# untitled.net
KiCad netlist of a schematic drawn in EAGLE
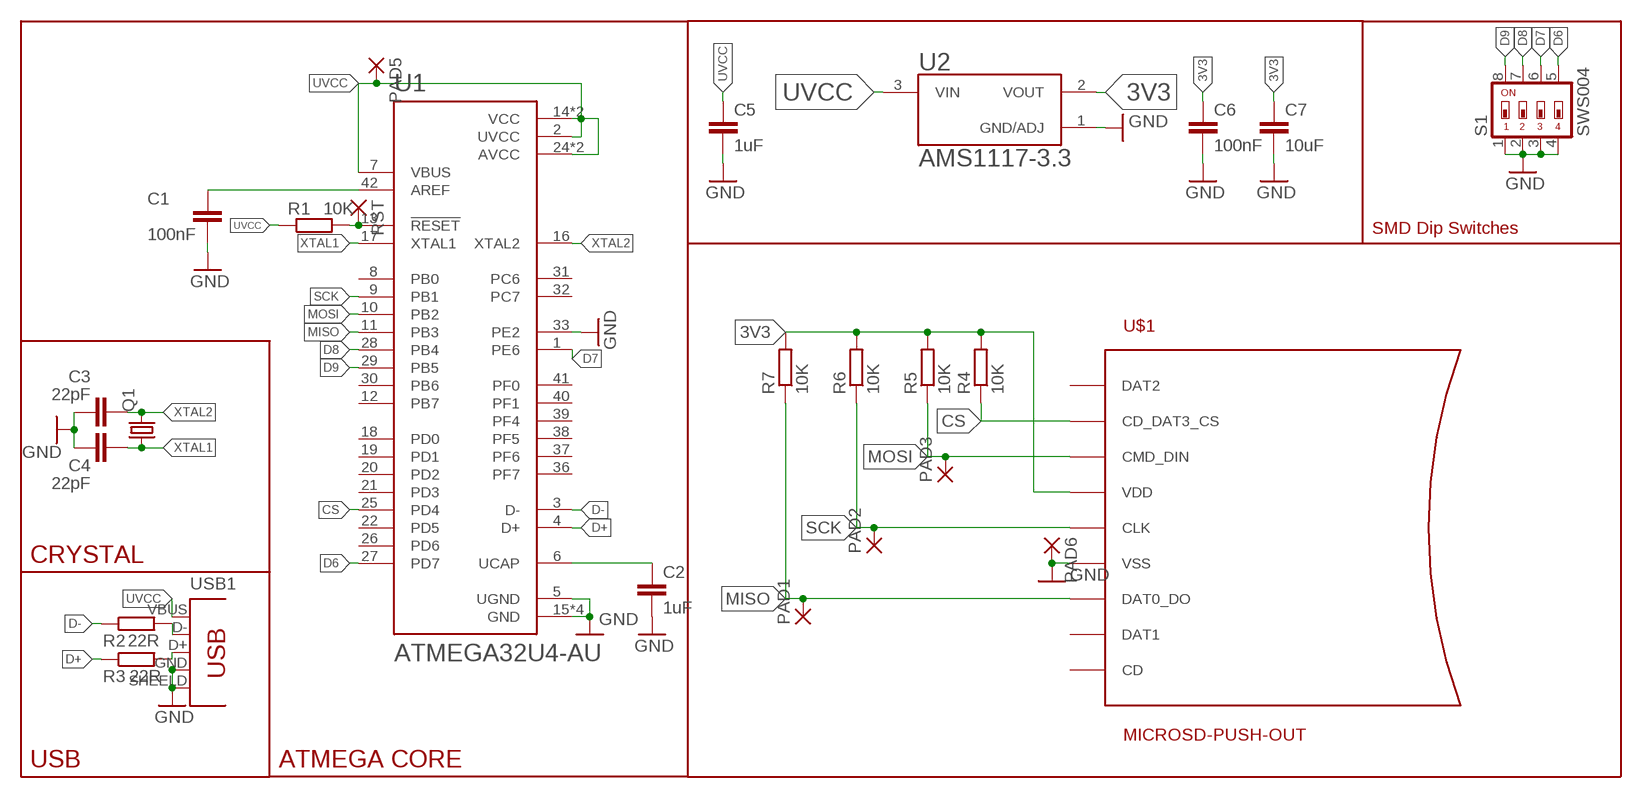
[diagram p0: schematic, sheet 1]

(export (version "E")
  (design (tool "Eeschema 10.0.6"))
  (components
    (comp (ref "C1")
      (value "100nF")
      (footprint "eagle-import:C0603")
      (libsource (lib "eagle-import") (part "C-EUC0603"))
    )
    (comp (ref "C2")
      (value "1uF")
      (footprint "eagle-import:C0603")
      (libsource (lib "eagle-import") (part "C-EUC0603"))
    )
    (comp (ref "C3")
      (value "22pF")
      (footprint "eagle-import:C0603")
      (libsource (lib "eagle-import") (part "C-EUC0603"))
    )
    (comp (ref "C4")
      (value "22pF")
      (footprint "eagle-import:C0603")
      (libsource (lib "eagle-import") (part "C-EUC0603"))
    )
    (comp (ref "C5")
      (value "1uF")
      (footprint "eagle-import:C0603")
      (libsource (lib "eagle-import") (part "C-EUC0603"))
    )
    (comp (ref "C6")
      (value "100nF")
      (footprint "eagle-import:C0603")
      (libsource (lib "eagle-import") (part "C-EUC0603"))
    )
    (comp (ref "C7")
      (value "10uF")
      (footprint "eagle-import:C0603")
      (libsource (lib "eagle-import") (part "C-EUC0603"))
    )
    (comp (ref "PAD1")
      (value "1,6/0,8")
      (footprint "eagle-import:1,6_0,8")
      (libsource (lib "eagle-import") (part "1,6/0,8"))
    )
    (comp (ref "PAD2")
      (value "1,6/0,8")
      (footprint "eagle-import:1,6_0,8")
      (libsource (lib "eagle-import") (part "1,6/0,8"))
    )
    (comp (ref "PAD3")
      (value "1,6/0,8")
      (footprint "eagle-import:1,6_0,8")
      (libsource (lib "eagle-import") (part "1,6/0,8"))
    )
    (comp (ref "PAD5")
      (value "1,6/0,8")
      (footprint "eagle-import:1,6_0,8")
      (libsource (lib "eagle-import") (part "1,6/0,8"))
    )
    (comp (ref "PAD6")
      (value "1,6/0,8")
      (footprint "eagle-import:1,6_0,8")
      (libsource (lib "eagle-import") (part "1,6/0,8"))
    )
    (comp (ref "Q1")
      (value "CRYSTALCTS406")
      (footprint "eagle-import:CTS406")
      (libsource (lib "eagle-import") (part "CRYSTALCTS406"))
    )
    (comp (ref "R1")
      (value "10K")
      (footprint "eagle-import:R0603")
      (libsource (lib "eagle-import") (part "R-EU_R0603"))
    )
    (comp (ref "R2")
      (value "22R")
      (footprint "eagle-import:R0603")
      (libsource (lib "eagle-import") (part "R-EU_R0603"))
    )
    (comp (ref "R3")
      (value "22R")
      (footprint "eagle-import:R0603")
      (libsource (lib "eagle-import") (part "R-EU_R0603"))
    )
    (comp (ref "R4")
      (value "10K")
      (footprint "eagle-import:R0603")
      (libsource (lib "eagle-import") (part "R-EU_R0603"))
    )
    (comp (ref "R5")
      (value "10K")
      (footprint "eagle-import:R0603")
      (libsource (lib "eagle-import") (part "R-EU_R0603"))
    )
    (comp (ref "R6")
      (value "10K")
      (footprint "eagle-import:R0603")
      (libsource (lib "eagle-import") (part "R-EU_R0603"))
    )
    (comp (ref "R7")
      (value "10K")
      (footprint "eagle-import:R0603")
      (libsource (lib "eagle-import") (part "R-EU_R0603"))
    )
    (comp (ref "RST")
      (value "1,6/0,8")
      (footprint "eagle-import:1,6_0,8")
      (libsource (lib "eagle-import") (part "1,6/0,8"))
    )
    (comp (ref "S1")
      (value "SWS004")
      (footprint "eagle-import:SMS-004")
      (libsource (lib "eagle-import") (part "SWS004"))
    )
    (comp (ref "U$1")
      (value "MICROSD-PUSH-OUT")
      (footprint "eagle-import:MICROSD-PUSH-OUT")
      (libsource (lib "eagle-import") (part "MICROSD-PUSH-OUT"))
    )
    (comp (ref "U1")
      (value "ATMEGA32U4-AU")
      (footprint "eagle-import:QFP80P1200X1200X120-44N")
      (fields (field (name "MF") "Microchip"))
      (libsource (lib "eagle-import") (part "ATMEGA32U4-AU"))
    )
    (comp (ref "U2")
      (value "AMS1117-3.3")
      (footprint "eagle-import:SOT229P700X180-4N")
      (fields (field (name "MF") "Advanced Monolithic Systems"))
      (libsource (lib "eagle-import") (part "AMS1117-3.3"))
    )
    (comp (ref "USB1")
      (value "TYPE-A-MALE-SHILED")
      (footprint "eagle-import:TYPE-A-MALE")
      (libsource (lib "eagle-import") (part "TYPE-A-MALE-SHILED"))
    )
  )
  (nets
    (net (code "1") (name "3V3") (class "Default")
      (node (ref "C6") (pin "1") (pinfunction "1_1") (pintype "passive"))
      (node (ref "C7") (pin "1") (pinfunction "1_1") (pintype "passive"))
      (node (ref "R4") (pin "2") (pinfunction "2_2") (pintype "passive"))
      (node (ref "R5") (pin "2") (pinfunction "2_2") (pintype "passive"))
      (node (ref "R6") (pin "2") (pinfunction "2_2") (pintype "passive"))
      (node (ref "R7") (pin "2") (pinfunction "2_2") (pintype "passive"))
      (node (ref "U$1") (pin "4") (pinfunction "VDD_4") (pintype "bidirectional"))
      (node (ref "U2") (pin "2") (pinfunction "VOUT_2") (pintype "output"))
    )
    (net (code "2") (name "CS") (class "Default")
      (node (ref "R4") (pin "1") (pinfunction "1_1") (pintype "passive"))
      (node (ref "U$1") (pin "2") (pinfunction "CD_DAT3_CS_2") (pintype "bidirectional"))
      (node (ref "U1") (pin "25") (pinfunction "PD4_25") (pintype "bidirectional"))
    )
    (net (code "3") (name "D+") (class "Default")
      (node (ref "R3") (pin "1") (pinfunction "1_1") (pintype "passive"))
      (node (ref "U1") (pin "4") (pinfunction "D+_4") (pintype "bidirectional"))
    )
    (net (code "4") (name "D-") (class "Default")
      (node (ref "R2") (pin "1") (pinfunction "1_1") (pintype "passive"))
      (node (ref "U1") (pin "3") (pinfunction "D-_3") (pintype "bidirectional"))
    )
    (net (code "5") (name "D6") (class "Default")
      (node (ref "S1") (pin "5") (pinfunction "5_5") (pintype "passive"))
      (node (ref "U1") (pin "27") (pinfunction "PD7_27") (pintype "bidirectional"))
    )
    (net (code "6") (name "D7") (class "Default")
      (node (ref "S1") (pin "6") (pinfunction "6_6") (pintype "passive"))
      (node (ref "U1") (pin "1") (pinfunction "PE6_1") (pintype "bidirectional"))
    )
    (net (code "7") (name "D8") (class "Default")
      (node (ref "S1") (pin "7") (pinfunction "7_7") (pintype "passive"))
      (node (ref "U1") (pin "28") (pinfunction "PB4_28") (pintype "bidirectional"))
    )
    (net (code "8") (name "D9") (class "Default")
      (node (ref "S1") (pin "8") (pinfunction "8_8") (pintype "passive"))
      (node (ref "U1") (pin "29") (pinfunction "PB5_29") (pintype "bidirectional"))
    )
    (net (code "9") (name "GND") (class "Default")
      (node (ref "C1") (pin "2") (pinfunction "2_2") (pintype "passive"))
      (node (ref "C2") (pin "2") (pinfunction "2_2") (pintype "passive"))
      (node (ref "C3") (pin "1") (pinfunction "1_1") (pintype "passive"))
      (node (ref "C4") (pin "1") (pinfunction "1_1") (pintype "passive"))
      (node (ref "C5") (pin "2") (pinfunction "2_2") (pintype "passive"))
      (node (ref "C6") (pin "2") (pinfunction "2_2") (pintype "passive"))
      (node (ref "C7") (pin "2") (pinfunction "2_2") (pintype "passive"))
      (node (ref "PAD6") (pin "1") (pinfunction "P_1") (pintype "passive"))
      (node (ref "S1") (pin "1") (pinfunction "1_1") (pintype "passive"))
      (node (ref "S1") (pin "2") (pinfunction "2_2") (pintype "passive"))
      (node (ref "S1") (pin "3") (pinfunction "3_3") (pintype "passive"))
      (node (ref "S1") (pin "4") (pinfunction "4_4") (pintype "passive"))
      (node (ref "U$1") (pin "6") (pinfunction "VSS_6") (pintype "bidirectional"))
      (node (ref "U$1") (pin "G1") (pinfunction "VSS_G1") (pintype "bidirectional"))
      (node (ref "U$1") (pin "G2") (pinfunction "VSS_G2") (pintype "bidirectional"))
      (node (ref "U$1") (pin "G3") (pinfunction "VSS_G3") (pintype "bidirectional"))
      (node (ref "U$1") (pin "G4") (pinfunction "VSS_G4") (pintype "bidirectional"))
      (node (ref "U1") (pin "15") (pinfunction "GND_15") (pintype "power_in"))
      (node (ref "U1") (pin "23") (pinfunction "GND_23") (pintype "power_in"))
      (node (ref "U1") (pin "33") (pinfunction "PE2_33") (pintype "bidirectional"))
      (node (ref "U1") (pin "35") (pinfunction "GND_35") (pintype "power_in"))
      (node (ref "U1") (pin "43") (pinfunction "GND_43") (pintype "power_in"))
      (node (ref "U1") (pin "5") (pinfunction "UGND_5") (pintype "power_in"))
      (node (ref "U2") (pin "1") (pinfunction "GND/ADJ_1") (pintype "power_in"))
      (node (ref "USB1") (pin "GND") (pinfunction "4_GND") (pintype "power_in"))
      (node (ref "USB1") (pin "SHEELD") (pinfunction "5_SHEELD") (pintype "passive"))
    )
    (net (code "10") (name "MISO") (class "Default")
      (node (ref "PAD1") (pin "1") (pinfunction "P_1") (pintype "passive"))
      (node (ref "R7") (pin "1") (pinfunction "1_1") (pintype "passive"))
      (node (ref "U$1") (pin "7") (pinfunction "DAT0_DO_7") (pintype "bidirectional"))
      (node (ref "U1") (pin "11") (pinfunction "PB3_11") (pintype "bidirectional"))
    )
    (net (code "11") (name "MOSI") (class "Default")
      (node (ref "PAD3") (pin "1") (pinfunction "P_1") (pintype "passive"))
      (node (ref "R5") (pin "1") (pinfunction "1_1") (pintype "passive"))
      (node (ref "U$1") (pin "3") (pinfunction "CMD_DIN_3") (pintype "bidirectional"))
      (node (ref "U1") (pin "10") (pinfunction "PB2_10") (pintype "bidirectional"))
    )
    (net (code "12") (name "Net-(RST-P)") (class "Default")
      (node (ref "R1") (pin "2") (pinfunction "2_2") (pintype "passive"))
      (node (ref "RST") (pin "1") (pinfunction "P_1") (pintype "passive"))
      (node (ref "U1") (pin "13") (pinfunction "~{RESET}_13") (pintype "input"))
    )
    (net (code "13") (name "Net-(U1-AREF)") (class "Default")
      (node (ref "C1") (pin "1") (pinfunction "1_1") (pintype "passive"))
      (node (ref "U1") (pin "42") (pinfunction "AREF_42") (pintype "input"))
    )
    (net (code "14") (name "Net-(U1-UCAP)") (class "Default")
      (node (ref "C2") (pin "1") (pinfunction "1_1") (pintype "passive"))
      (node (ref "U1") (pin "6") (pinfunction "UCAP_6") (pintype "passive"))
    )
    (net (code "15") (name "Net-(USB1-2)") (class "Default")
      (node (ref "R2") (pin "2") (pinfunction "2_2") (pintype "passive"))
      (node (ref "USB1") (pin "D-") (pinfunction "2_D-") (pintype "passive"))
    )
    (net (code "16") (name "Net-(USB1-3)") (class "Default")
      (node (ref "R3") (pin "2") (pinfunction "2_2") (pintype "passive"))
      (node (ref "USB1") (pin "D+") (pinfunction "3_D+") (pintype "passive"))
    )
    (net (code "17") (name "SCK") (class "Default")
      (node (ref "PAD2") (pin "1") (pinfunction "P_1") (pintype "passive"))
      (node (ref "R6") (pin "1") (pinfunction "1_1") (pintype "passive"))
      (node (ref "U$1") (pin "5") (pinfunction "CLK_5") (pintype "bidirectional"))
      (node (ref "U1") (pin "9") (pinfunction "PB1_9") (pintype "bidirectional"))
    )
    (net (code "18") (name "UVCC") (class "Default")
      (node (ref "C5") (pin "1") (pinfunction "1_1") (pintype "passive"))
      (node (ref "PAD5") (pin "1") (pinfunction "P_1") (pintype "passive"))
      (node (ref "R1") (pin "1") (pinfunction "1_1") (pintype "passive"))
      (node (ref "U1") (pin "14") (pinfunction "VCC_14") (pintype "power_in"))
      (node (ref "U1") (pin "2") (pinfunction "UVCC_2") (pintype "power_in"))
      (node (ref "U1") (pin "24") (pinfunction "AVCC_24") (pintype "power_in"))
      (node (ref "U1") (pin "34") (pinfunction "VCC_34") (pintype "power_in"))
      (node (ref "U1") (pin "44") (pinfunction "AVCC_44") (pintype "power_in"))
      (node (ref "U1") (pin "7") (pinfunction "VBUS_7") (pintype "input"))
      (node (ref "U2") (pin "3") (pinfunction "VIN_3") (pintype "input"))
      (node (ref "USB1") (pin "VBUS") (pinfunction "1_VBUS") (pintype "power_in"))
    )
    (net (code "19") (name "XTAL1") (class "Default")
      (node (ref "C4") (pin "2") (pinfunction "2_2") (pintype "passive"))
      (node (ref "Q1") (pin "1") (pinfunction "1_1") (pintype "passive"))
      (node (ref "U1") (pin "17") (pinfunction "XTAL1_17") (pintype "input"))
    )
    (net (code "20") (name "XTAL2") (class "Default")
      (node (ref "C3") (pin "2") (pinfunction "2_2") (pintype "passive"))
      (node (ref "Q1") (pin "3") (pinfunction "2_3") (pintype "passive"))
      (node (ref "U1") (pin "16") (pinfunction "XTAL2_16") (pintype "output"))
    )
    (net (code "21") (name "unconnected-(U$1-DAT1-Pad8)") (class "Default")
      (node (ref "U$1") (pin "8") (pinfunction "DAT1_8") (pintype "bidirectional"))
    )
    (net (code "22") (name "unconnected-(U$1-DAT2-Pad1)") (class "Default")
      (node (ref "U$1") (pin "1") (pinfunction "DAT2_1") (pintype "bidirectional"))
    )
    (net (code "23") (name "unconnected-(U$1-PadCD)") (class "Default")
      (node (ref "U$1") (pin "CD") (pinfunction "CD_CD") (pintype "bidirectional"))
    )
    (net (code "24") (name "unconnected-(U1-PB0-Pad8)") (class "Default")
      (node (ref "U1") (pin "8") (pinfunction "PB0_8") (pintype "bidirectional"))
    )
    (net (code "25") (name "unconnected-(U1-PB6-Pad30)") (class "Default")
      (node (ref "U1") (pin "30") (pinfunction "PB6_30") (pintype "bidirectional"))
    )
    (net (code "26") (name "unconnected-(U1-PB7-Pad12)") (class "Default")
      (node (ref "U1") (pin "12") (pinfunction "PB7_12") (pintype "bidirectional"))
    )
    (net (code "27") (name "unconnected-(U1-PC6-Pad31)") (class "Default")
      (node (ref "U1") (pin "31") (pinfunction "PC6_31") (pintype "bidirectional"))
    )
    (net (code "28") (name "unconnected-(U1-PC7-Pad32)") (class "Default")
      (node (ref "U1") (pin "32") (pinfunction "PC7_32") (pintype "bidirectional"))
    )
    (net (code "29") (name "unconnected-(U1-PD0-Pad18)") (class "Default")
      (node (ref "U1") (pin "18") (pinfunction "PD0_18") (pintype "bidirectional"))
    )
    (net (code "30") (name "unconnected-(U1-PD1-Pad19)") (class "Default")
      (node (ref "U1") (pin "19") (pinfunction "PD1_19") (pintype "bidirectional"))
    )
    (net (code "31") (name "unconnected-(U1-PD2-Pad20)") (class "Default")
      (node (ref "U1") (pin "20") (pinfunction "PD2_20") (pintype "bidirectional"))
    )
    (net (code "32") (name "unconnected-(U1-PD3-Pad21)") (class "Default")
      (node (ref "U1") (pin "21") (pinfunction "PD3_21") (pintype "bidirectional"))
    )
    (net (code "33") (name "unconnected-(U1-PD5-Pad22)") (class "Default")
      (node (ref "U1") (pin "22") (pinfunction "PD5_22") (pintype "bidirectional"))
    )
    (net (code "34") (name "unconnected-(U1-PD6-Pad26)") (class "Default")
      (node (ref "U1") (pin "26") (pinfunction "PD6_26") (pintype "bidirectional"))
    )
    (net (code "35") (name "unconnected-(U1-PF0-Pad41)") (class "Default")
      (node (ref "U1") (pin "41") (pinfunction "PF0_41") (pintype "bidirectional"))
    )
    (net (code "36") (name "unconnected-(U1-PF1-Pad40)") (class "Default")
      (node (ref "U1") (pin "40") (pinfunction "PF1_40") (pintype "bidirectional"))
    )
    (net (code "37") (name "unconnected-(U1-PF4-Pad39)") (class "Default")
      (node (ref "U1") (pin "39") (pinfunction "PF4_39") (pintype "bidirectional"))
    )
    (net (code "38") (name "unconnected-(U1-PF5-Pad38)") (class "Default")
      (node (ref "U1") (pin "38") (pinfunction "PF5_38") (pintype "bidirectional"))
    )
    (net (code "39") (name "unconnected-(U1-PF6-Pad37)") (class "Default")
      (node (ref "U1") (pin "37") (pinfunction "PF6_37") (pintype "bidirectional"))
    )
    (net (code "40") (name "unconnected-(U1-PF7-Pad36)") (class "Default")
      (node (ref "U1") (pin "36") (pinfunction "PF7_36") (pintype "bidirectional"))
    )
  )
)
